# protoCuantumv2_1.net
KiCad netlist of a schematic drawn in EAGLE
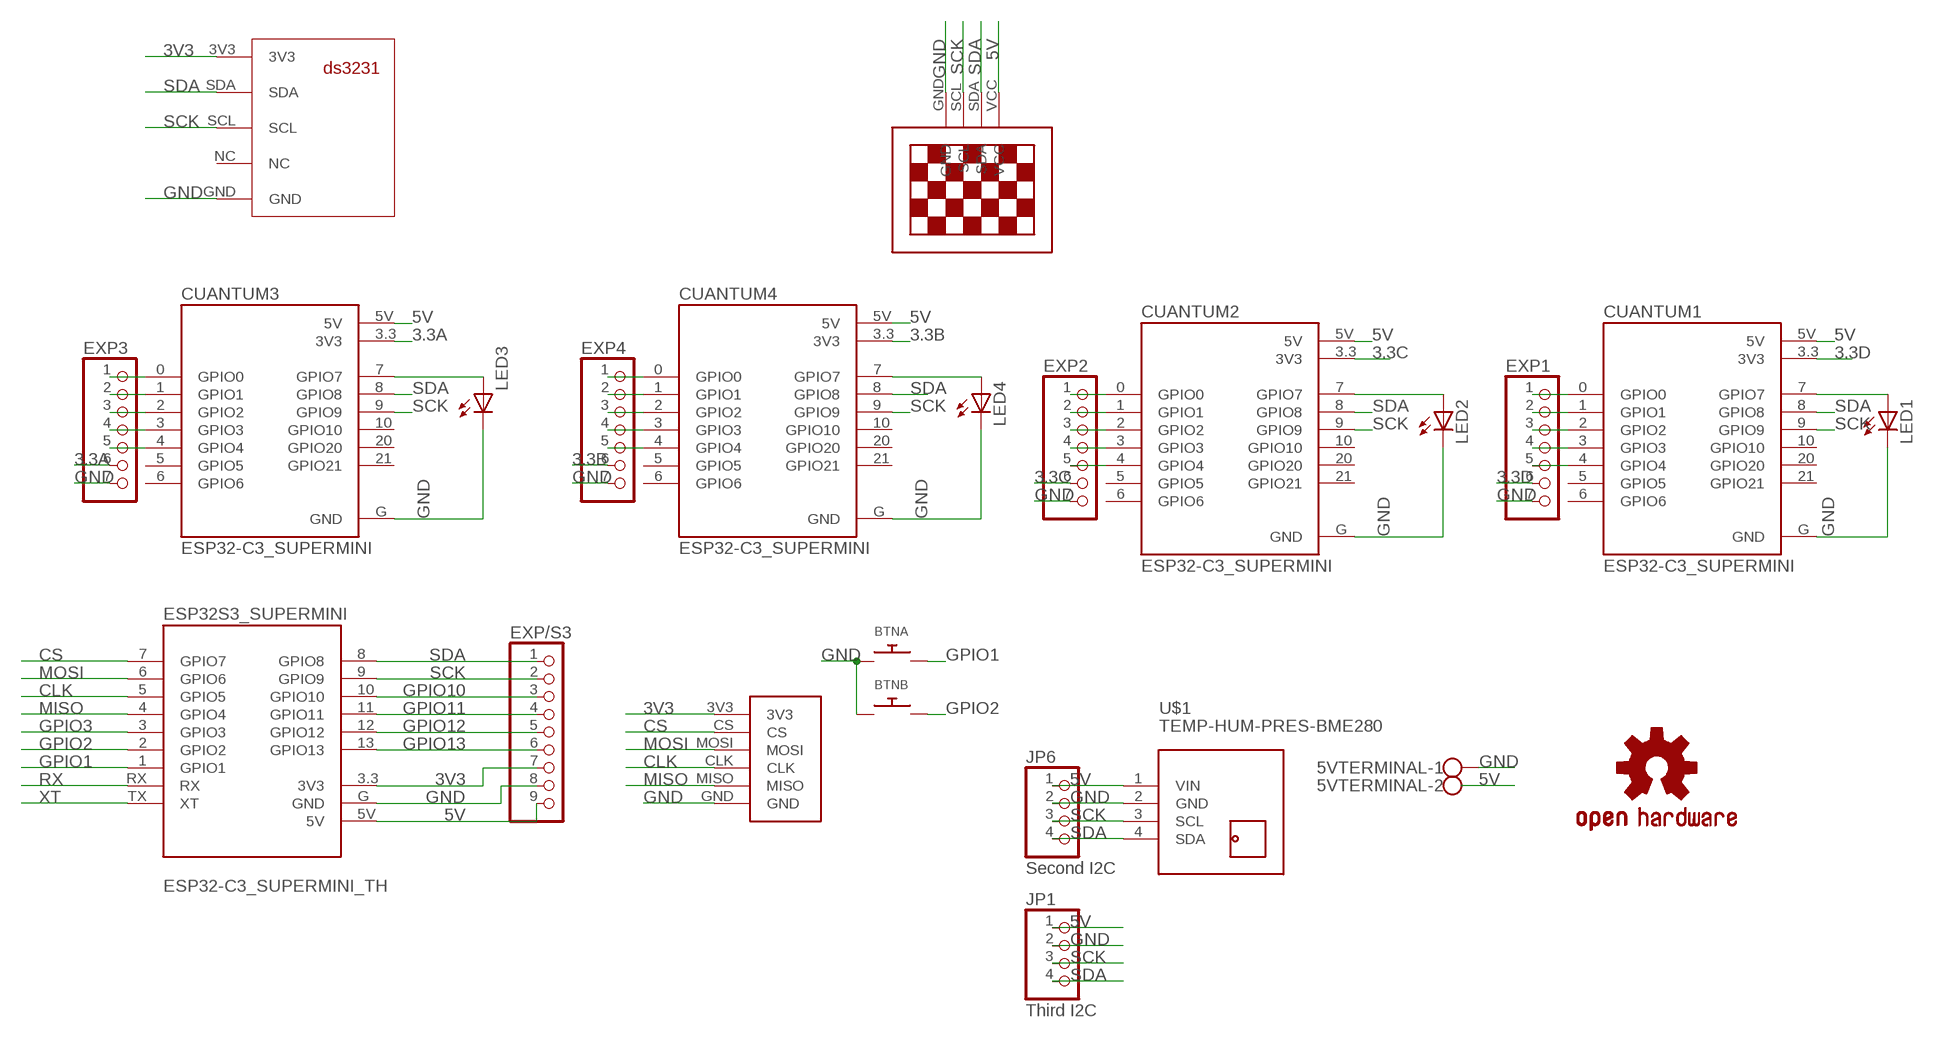
[diagram p0: schematic, sheet 1]

(export (version "E")
  (design (tool "Eeschema 10.0.6"))
  (components
    (comp (ref "5VTERMINAL")
      (value "W237-102")
      (footprint "eagle-import:W237-102")
      (fields (field (name "MPN") "237-102"))
      (libsource (lib "eagle-import") (part "W237-102"))
    )
    (comp (ref "BTNA")
      (value "SWITCH_PUSHBUTTONEVQ-PE")
      (footprint "eagle-import:TACT_PANA-EVQ")
      (libsource (lib "eagle-import") (part "SWITCH_PUSHBUTTONEVQ-PE"))
    )
    (comp (ref "BTNB")
      (value "SWITCH_PUSHBUTTONEVQ-PE")
      (footprint "eagle-import:TACT_PANA-EVQ")
      (libsource (lib "eagle-import") (part "SWITCH_PUSHBUTTONEVQ-PE"))
    )
    (comp (ref "CUANTUM1")
      (value "ESP32-C3_SUPERMINI")
      (footprint "eagle-import:MODULE_ESP32-C3_SUPERMINI_TH")
      (fields (field (name "MF") "Espressif Systems") (field (name "MP") "ESP32-C3 SuperMini_TH"))
      (libsource (lib "eagle-import") (part "ESP32-C3_SUPERMINI_TH"))
    )
    (comp (ref "CUANTUM2")
      (value "ESP32-C3_SUPERMINI")
      (footprint "eagle-import:MODULE_ESP32-C3_SUPERMINI_TH")
      (fields (field (name "MF") "Espressif Systems") (field (name "MP") "ESP32-C3 SuperMini_TH"))
      (libsource (lib "eagle-import") (part "ESP32-C3_SUPERMINI_TH"))
    )
    (comp (ref "CUANTUM3")
      (value "ESP32-C3_SUPERMINI")
      (footprint "eagle-import:MODULE_ESP32-C3_SUPERMINI_TH")
      (fields (field (name "MF") "Espressif Systems") (field (name "MP") "ESP32-C3 SuperMini_TH"))
      (libsource (lib "eagle-import") (part "ESP32-C3_SUPERMINI_TH"))
    )
    (comp (ref "CUANTUM4")
      (value "ESP32-C3_SUPERMINI")
      (footprint "eagle-import:MODULE_ESP32-C3_SUPERMINI_TH")
      (fields (field (name "MF") "Espressif Systems") (field (name "MP") "ESP32-C3 SuperMini_TH"))
      (libsource (lib "eagle-import") (part "ESP32-C3_SUPERMINI_TH"))
    )
    (comp (ref "ESP32S3_SUPERMINI")
      (value "ESP32-C3_SUPERMINI_TH")
      (footprint "eagle-import:MODULE_ESP32-C3_SUPERMINI_TH")
      (fields (field (name "MF") "Espressif Systems") (field (name "MP") "ESP32-S3 SuperMini_TH"))
      (libsource (lib "eagle-import") (part "ESP32-S3_SUPERMINI_TH_ESP32-C3_SUPERMINI_TH"))
    )
    (comp (ref "EXP/S3")
      (value "PINHD-1X9")
      (footprint "eagle-import:1X09")
      (libsource (lib "eagle-import") (part "PINHD-1X9"))
    )
    (comp (ref "EXP1")
      (value "PINHD-1X7")
      (footprint "eagle-import:1X07")
      (libsource (lib "eagle-import") (part "PINHD-1X7"))
    )
    (comp (ref "EXP2")
      (value "PINHD-1X7")
      (footprint "eagle-import:1X07")
      (libsource (lib "eagle-import") (part "PINHD-1X7"))
    )
    (comp (ref "EXP3")
      (value "PINHD-1X7")
      (footprint "eagle-import:1X07")
      (libsource (lib "eagle-import") (part "PINHD-1X7"))
    )
    (comp (ref "EXP4")
      (value "PINHD-1X7")
      (footprint "eagle-import:1X07")
      (libsource (lib "eagle-import") (part "PINHD-1X7"))
    )
    (comp (ref "JP1")
      (value "Third I2C")
      (footprint "eagle-import:1X04")
      (libsource (lib "eagle-import") (part "PINHD-1X4"))
    )
    (comp (ref "JP6")
      (value "Second I2C")
      (footprint "eagle-import:1X04")
      (libsource (lib "eagle-import") (part "PINHD-1X4"))
    )
    (comp (ref "LED1")
      (value "LED3MM")
      (footprint "eagle-import:LED3MM")
      (libsource (lib "eagle-import") (part "LED3MM"))
    )
    (comp (ref "LED2")
      (value "LED3MM")
      (footprint "eagle-import:LED3MM")
      (libsource (lib "eagle-import") (part "LED3MM"))
    )
    (comp (ref "LED3")
      (value "LED3MM")
      (footprint "eagle-import:LED3MM")
      (libsource (lib "eagle-import") (part "LED3MM"))
    )
    (comp (ref "LED4")
      (value "LED3MM")
      (footprint "eagle-import:LED3MM")
      (libsource (lib "eagle-import") (part "LED3MM"))
    )
    (comp (ref "LOGO1")
      (value "OSHW-LOGOM")
      (footprint "eagle-import:OSHW-LOGO-M")
      (libsource (lib "eagle-import") (part "OSHW-LOGOM"))
    )
    (comp (ref "OLED1.3")
      (value "13\"OLED13\"OLED")
      (footprint "eagle-import:1.3_OLED")
      (libsource (lib "eagle-import") (part "13{dblquote}OLED13{dblquote}OLED"))
    )
    (comp (ref "U$1")
      (value "TEMP-HUM-PRES-BME280")
      (footprint "eagle-import:TEMP-HUM-PRES-BME280")
      (libsource (lib "eagle-import") (part "TEMP-HUM-PRES-BME280"))
    )
    (comp (ref "U$2")
      (value "SD_KUSKALLA")
      (footprint "eagle-import:SD_KUSKALLA")
      (libsource (lib "eagle-import") (part "SD_KUSKALLA"))
    )
    (comp (ref "U$4")
      (value "RTC")
      (footprint "eagle-import:RTCDS3231FP")
      (libsource (lib "eagle-import") (part "RTC"))
    )
  )
  (nets
    (net (code "1") (name "/3.3A") (class "Default")
      (node (ref "CUANTUM3") (pin "3.3") (pinfunction "3V3_3.3") (pintype "power_in"))
      (node (ref "EXP3") (pin "6") (pinfunction "6_6") (pintype "passive"))
    )
    (net (code "2") (name "/3.3B") (class "Default")
      (node (ref "CUANTUM4") (pin "3.3") (pinfunction "3V3_3.3") (pintype "power_in"))
      (node (ref "EXP4") (pin "6") (pinfunction "6_6") (pintype "passive"))
    )
    (net (code "3") (name "/3.3C") (class "Default")
      (node (ref "CUANTUM2") (pin "3.3") (pinfunction "3V3_3.3") (pintype "power_in"))
      (node (ref "EXP2") (pin "6") (pinfunction "6_6") (pintype "passive"))
    )
    (net (code "4") (name "/3.3D") (class "Default")
      (node (ref "CUANTUM1") (pin "3.3") (pinfunction "3V3_3.3") (pintype "power_in"))
      (node (ref "EXP1") (pin "6") (pinfunction "6_6") (pintype "passive"))
    )
    (net (code "5") (name "/3V3") (class "Default")
      (node (ref "ESP32S3_SUPERMINI") (pin "3.3") (pinfunction "3V3_3.3") (pintype "power_in"))
      (node (ref "EXP/S3") (pin "7") (pinfunction "7_7") (pintype "passive"))
      (node (ref "U$2") (pin "3V3") (pinfunction "3V3_3V3") (pintype "bidirectional"))
      (node (ref "U$4") (pin "3V3") (pinfunction "3V3_3V3") (pintype "bidirectional"))
    )
    (net (code "6") (name "/5V") (class "Default")
      (node (ref "5VTERMINAL") (pin "2") (pinfunction "KL_2") (pintype "passive"))
      (node (ref "CUANTUM1") (pin "5V") (pinfunction "5V_5V") (pintype "power_in"))
      (node (ref "CUANTUM2") (pin "5V") (pinfunction "5V_5V") (pintype "power_in"))
      (node (ref "CUANTUM3") (pin "5V") (pinfunction "5V_5V") (pintype "power_in"))
      (node (ref "CUANTUM4") (pin "5V") (pinfunction "5V_5V") (pintype "power_in"))
      (node (ref "ESP32S3_SUPERMINI") (pin "5V") (pinfunction "5V_5V") (pintype "power_in"))
      (node (ref "EXP/S3") (pin "9") (pinfunction "9_9") (pintype "passive"))
      (node (ref "JP1") (pin "1") (pinfunction "1_1") (pintype "passive"))
      (node (ref "JP6") (pin "1") (pinfunction "1_1") (pintype "passive"))
      (node (ref "OLED1.3") (pin "VCC") (pinfunction "VCC_VCC") (pintype "bidirectional"))
      (node (ref "U$1") (pin "1") (pinfunction "VIN_1") (pintype "power_in"))
    )
    (net (code "7") (name "/CLK") (class "Default")
      (node (ref "ESP32S3_SUPERMINI") (pin "5") (pinfunction "GPIO5_5") (pintype "bidirectional"))
      (node (ref "U$2") (pin "CLK") (pinfunction "CLK_CLK") (pintype "bidirectional"))
    )
    (net (code "8") (name "/CS") (class "Default")
      (node (ref "ESP32S3_SUPERMINI") (pin "7") (pinfunction "GPIO7_7") (pintype "bidirectional"))
      (node (ref "U$2") (pin "CS") (pinfunction "CS_CS") (pintype "bidirectional"))
    )
    (net (code "9") (name "/GND") (class "Default")
      (node (ref "5VTERMINAL") (pin "1") (pinfunction "KL_1") (pintype "passive"))
      (node (ref "BTNA") (pin "P$1") (pinfunction "P$1_P$1") (pintype "passive"))
      (node (ref "BTNB") (pin "P$1") (pinfunction "P$1_P$1") (pintype "passive"))
      (node (ref "CUANTUM1") (pin "G") (pinfunction "GND_G") (pintype "power_in"))
      (node (ref "CUANTUM2") (pin "G") (pinfunction "GND_G") (pintype "power_in"))
      (node (ref "CUANTUM3") (pin "G") (pinfunction "GND_G") (pintype "power_in"))
      (node (ref "CUANTUM4") (pin "G") (pinfunction "GND_G") (pintype "power_in"))
      (node (ref "ESP32S3_SUPERMINI") (pin "G") (pinfunction "GND_G") (pintype "power_in"))
      (node (ref "EXP/S3") (pin "8") (pinfunction "8_8") (pintype "passive"))
      (node (ref "EXP1") (pin "7") (pinfunction "7_7") (pintype "passive"))
      (node (ref "EXP2") (pin "7") (pinfunction "7_7") (pintype "passive"))
      (node (ref "EXP3") (pin "7") (pinfunction "7_7") (pintype "passive"))
      (node (ref "EXP4") (pin "7") (pinfunction "7_7") (pintype "passive"))
      (node (ref "JP1") (pin "2") (pinfunction "2_2") (pintype "passive"))
      (node (ref "JP6") (pin "2") (pinfunction "2_2") (pintype "passive"))
      (node (ref "LED1") (pin "K") (pinfunction "C_K") (pintype "passive"))
      (node (ref "LED2") (pin "K") (pinfunction "C_K") (pintype "passive"))
      (node (ref "LED3") (pin "K") (pinfunction "C_K") (pintype "passive"))
      (node (ref "LED4") (pin "K") (pinfunction "C_K") (pintype "passive"))
      (node (ref "OLED1.3") (pin "GND") (pinfunction "GND_GND") (pintype "bidirectional"))
      (node (ref "U$1") (pin "2") (pinfunction "GND_2") (pintype "power_in"))
      (node (ref "U$2") (pin "GND") (pinfunction "GND_GND") (pintype "bidirectional"))
      (node (ref "U$4") (pin "GND") (pinfunction "GND_GND") (pintype "bidirectional"))
    )
    (net (code "10") (name "/GPIO1") (class "Default")
      (node (ref "BTNA") (pin "P$2") (pinfunction "P$2_P$2") (pintype "passive"))
      (node (ref "ESP32S3_SUPERMINI") (pin "1") (pinfunction "GPIO1_1") (pintype "bidirectional"))
    )
    (net (code "11") (name "/GPIO2") (class "Default")
      (node (ref "BTNB") (pin "P$2") (pinfunction "P$2_P$2") (pintype "passive"))
      (node (ref "ESP32S3_SUPERMINI") (pin "2") (pinfunction "GPIO2_2") (pintype "bidirectional"))
    )
    (net (code "12") (name "/GPIO3") (class "Default")
      (node (ref "ESP32S3_SUPERMINI") (pin "3") (pinfunction "GPIO3_3") (pintype "bidirectional"))
    )
    (net (code "13") (name "/GPIO10") (class "Default")
      (node (ref "ESP32S3_SUPERMINI") (pin "10") (pinfunction "GPIO10_10") (pintype "bidirectional"))
      (node (ref "EXP/S3") (pin "3") (pinfunction "3_3") (pintype "passive"))
    )
    (net (code "14") (name "/GPIO11") (class "Default")
      (node (ref "ESP32S3_SUPERMINI") (pin "11") (pinfunction "GPIO11_11") (pintype "bidirectional"))
      (node (ref "EXP/S3") (pin "4") (pinfunction "4_4") (pintype "passive"))
    )
    (net (code "15") (name "/GPIO12") (class "Default")
      (node (ref "ESP32S3_SUPERMINI") (pin "12") (pinfunction "GPIO12_12") (pintype "bidirectional"))
      (node (ref "EXP/S3") (pin "5") (pinfunction "5_5") (pintype "passive"))
    )
    (net (code "16") (name "/GPIO13") (class "Default")
      (node (ref "ESP32S3_SUPERMINI") (pin "13") (pinfunction "GPIO13_13") (pintype "bidirectional"))
      (node (ref "EXP/S3") (pin "6") (pinfunction "6_6") (pintype "passive"))
    )
    (net (code "17") (name "/MISO") (class "Default")
      (node (ref "ESP32S3_SUPERMINI") (pin "4") (pinfunction "GPIO4_4") (pintype "bidirectional"))
      (node (ref "U$2") (pin "MISO") (pinfunction "MISO_MISO") (pintype "bidirectional"))
    )
    (net (code "18") (name "/MOSI") (class "Default")
      (node (ref "ESP32S3_SUPERMINI") (pin "6") (pinfunction "GPIO6_6") (pintype "bidirectional"))
      (node (ref "U$2") (pin "MOSI") (pinfunction "MOSI_MOSI") (pintype "bidirectional"))
    )
    (net (code "19") (name "/RX") (class "Default")
      (node (ref "ESP32S3_SUPERMINI") (pin "RX") (pinfunction "RX_RX") (pintype "bidirectional"))
    )
    (net (code "20") (name "/SCK") (class "Default")
      (node (ref "CUANTUM1") (pin "9") (pinfunction "GPIO9_9") (pintype "bidirectional"))
      (node (ref "CUANTUM2") (pin "9") (pinfunction "GPIO9_9") (pintype "bidirectional"))
      (node (ref "CUANTUM3") (pin "9") (pinfunction "GPIO9_9") (pintype "bidirectional"))
      (node (ref "CUANTUM4") (pin "9") (pinfunction "GPIO9_9") (pintype "bidirectional"))
      (node (ref "ESP32S3_SUPERMINI") (pin "9") (pinfunction "GPIO9_9") (pintype "bidirectional"))
      (node (ref "EXP/S3") (pin "2") (pinfunction "2_2") (pintype "passive"))
      (node (ref "JP1") (pin "3") (pinfunction "3_3") (pintype "passive"))
      (node (ref "JP6") (pin "3") (pinfunction "3_3") (pintype "passive"))
      (node (ref "OLED1.3") (pin "SCL") (pinfunction "SCL_SCL") (pintype "bidirectional"))
      (node (ref "U$1") (pin "3") (pinfunction "SCL_3") (pintype "bidirectional"))
      (node (ref "U$4") (pin "SCL") (pinfunction "SCL_SCL") (pintype "bidirectional"))
    )
    (net (code "21") (name "/SDA") (class "Default")
      (node (ref "CUANTUM1") (pin "8") (pinfunction "GPIO8_8") (pintype "bidirectional"))
      (node (ref "CUANTUM2") (pin "8") (pinfunction "GPIO8_8") (pintype "bidirectional"))
      (node (ref "CUANTUM3") (pin "8") (pinfunction "GPIO8_8") (pintype "bidirectional"))
      (node (ref "CUANTUM4") (pin "8") (pinfunction "GPIO8_8") (pintype "bidirectional"))
      (node (ref "ESP32S3_SUPERMINI") (pin "8") (pinfunction "GPIO8_8") (pintype "bidirectional"))
      (node (ref "EXP/S3") (pin "1") (pinfunction "1_1") (pintype "passive"))
      (node (ref "JP1") (pin "4") (pinfunction "4_4") (pintype "passive"))
      (node (ref "JP6") (pin "4") (pinfunction "4_4") (pintype "passive"))
      (node (ref "OLED1.3") (pin "SDA") (pinfunction "SDA_SDA") (pintype "bidirectional"))
      (node (ref "U$1") (pin "4") (pinfunction "SDA_4") (pintype "bidirectional"))
      (node (ref "U$4") (pin "SDA") (pinfunction "SDA_SDA") (pintype "bidirectional"))
    )
    (net (code "22") (name "/XT") (class "Default")
      (node (ref "ESP32S3_SUPERMINI") (pin "TX") (pinfunction "XT_TX") (pintype "bidirectional"))
    )
    (net (code "23") (name "Net-(CUANTUM1-GPIO0)") (class "Default")
      (node (ref "CUANTUM1") (pin "0") (pinfunction "GPIO0_0") (pintype "bidirectional"))
      (node (ref "EXP1") (pin "1") (pinfunction "1_1") (pintype "passive"))
    )
    (net (code "24") (name "Net-(CUANTUM1-GPIO1)") (class "Default")
      (node (ref "CUANTUM1") (pin "1") (pinfunction "GPIO1_1") (pintype "bidirectional"))
      (node (ref "EXP1") (pin "2") (pinfunction "2_2") (pintype "passive"))
    )
    (net (code "25") (name "Net-(CUANTUM1-GPIO2)") (class "Default")
      (node (ref "CUANTUM1") (pin "2") (pinfunction "GPIO2_2") (pintype "bidirectional"))
      (node (ref "EXP1") (pin "3") (pinfunction "3_3") (pintype "passive"))
    )
    (net (code "26") (name "Net-(CUANTUM1-GPIO3)") (class "Default")
      (node (ref "CUANTUM1") (pin "3") (pinfunction "GPIO3_3") (pintype "bidirectional"))
      (node (ref "EXP1") (pin "4") (pinfunction "4_4") (pintype "passive"))
    )
    (net (code "27") (name "Net-(CUANTUM1-GPIO4)") (class "Default")
      (node (ref "CUANTUM1") (pin "4") (pinfunction "GPIO4_4") (pintype "bidirectional"))
      (node (ref "EXP1") (pin "5") (pinfunction "5_5") (pintype "passive"))
    )
    (net (code "28") (name "Net-(CUANTUM1-GPIO7)") (class "Default")
      (node (ref "CUANTUM1") (pin "7") (pinfunction "GPIO7_7") (pintype "bidirectional"))
      (node (ref "LED1") (pin "A") (pinfunction "A_A") (pintype "passive"))
    )
    (net (code "29") (name "Net-(CUANTUM2-GPIO0)") (class "Default")
      (node (ref "CUANTUM2") (pin "0") (pinfunction "GPIO0_0") (pintype "bidirectional"))
      (node (ref "EXP2") (pin "1") (pinfunction "1_1") (pintype "passive"))
    )
    (net (code "30") (name "Net-(CUANTUM2-GPIO1)") (class "Default")
      (node (ref "CUANTUM2") (pin "1") (pinfunction "GPIO1_1") (pintype "bidirectional"))
      (node (ref "EXP2") (pin "2") (pinfunction "2_2") (pintype "passive"))
    )
    (net (code "31") (name "Net-(CUANTUM2-GPIO2)") (class "Default")
      (node (ref "CUANTUM2") (pin "2") (pinfunction "GPIO2_2") (pintype "bidirectional"))
      (node (ref "EXP2") (pin "3") (pinfunction "3_3") (pintype "passive"))
    )
    (net (code "32") (name "Net-(CUANTUM2-GPIO3)") (class "Default")
      (node (ref "CUANTUM2") (pin "3") (pinfunction "GPIO3_3") (pintype "bidirectional"))
      (node (ref "EXP2") (pin "4") (pinfunction "4_4") (pintype "passive"))
    )
    (net (code "33") (name "Net-(CUANTUM2-GPIO4)") (class "Default")
      (node (ref "CUANTUM2") (pin "4") (pinfunction "GPIO4_4") (pintype "bidirectional"))
      (node (ref "EXP2") (pin "5") (pinfunction "5_5") (pintype "passive"))
    )
    (net (code "34") (name "Net-(CUANTUM2-GPIO7)") (class "Default")
      (node (ref "CUANTUM2") (pin "7") (pinfunction "GPIO7_7") (pintype "bidirectional"))
      (node (ref "LED2") (pin "A") (pinfunction "A_A") (pintype "passive"))
    )
    (net (code "35") (name "Net-(CUANTUM3-GPIO0)") (class "Default")
      (node (ref "CUANTUM3") (pin "0") (pinfunction "GPIO0_0") (pintype "bidirectional"))
      (node (ref "EXP3") (pin "1") (pinfunction "1_1") (pintype "passive"))
    )
    (net (code "36") (name "Net-(CUANTUM3-GPIO1)") (class "Default")
      (node (ref "CUANTUM3") (pin "1") (pinfunction "GPIO1_1") (pintype "bidirectional"))
      (node (ref "EXP3") (pin "2") (pinfunction "2_2") (pintype "passive"))
    )
    (net (code "37") (name "Net-(CUANTUM3-GPIO2)") (class "Default")
      (node (ref "CUANTUM3") (pin "2") (pinfunction "GPIO2_2") (pintype "bidirectional"))
      (node (ref "EXP3") (pin "3") (pinfunction "3_3") (pintype "passive"))
    )
    (net (code "38") (name "Net-(CUANTUM3-GPIO3)") (class "Default")
      (node (ref "CUANTUM3") (pin "3") (pinfunction "GPIO3_3") (pintype "bidirectional"))
      (node (ref "EXP3") (pin "4") (pinfunction "4_4") (pintype "passive"))
    )
    (net (code "39") (name "Net-(CUANTUM3-GPIO4)") (class "Default")
      (node (ref "CUANTUM3") (pin "4") (pinfunction "GPIO4_4") (pintype "bidirectional"))
      (node (ref "EXP3") (pin "5") (pinfunction "5_5") (pintype "passive"))
    )
    (net (code "40") (name "Net-(CUANTUM3-GPIO7)") (class "Default")
      (node (ref "CUANTUM3") (pin "7") (pinfunction "GPIO7_7") (pintype "bidirectional"))
      (node (ref "LED3") (pin "A") (pinfunction "A_A") (pintype "passive"))
    )
    (net (code "41") (name "Net-(CUANTUM4-GPIO0)") (class "Default")
      (node (ref "CUANTUM4") (pin "0") (pinfunction "GPIO0_0") (pintype "bidirectional"))
      (node (ref "EXP4") (pin "1") (pinfunction "1_1") (pintype "passive"))
    )
    (net (code "42") (name "Net-(CUANTUM4-GPIO1)") (class "Default")
      (node (ref "CUANTUM4") (pin "1") (pinfunction "GPIO1_1") (pintype "bidirectional"))
      (node (ref "EXP4") (pin "2") (pinfunction "2_2") (pintype "passive"))
    )
    (net (code "43") (name "Net-(CUANTUM4-GPIO2)") (class "Default")
      (node (ref "CUANTUM4") (pin "2") (pinfunction "GPIO2_2") (pintype "bidirectional"))
      (node (ref "EXP4") (pin "3") (pinfunction "3_3") (pintype "passive"))
    )
    (net (code "44") (name "Net-(CUANTUM4-GPIO3)") (class "Default")
      (node (ref "CUANTUM4") (pin "3") (pinfunction "GPIO3_3") (pintype "bidirectional"))
      (node (ref "EXP4") (pin "4") (pinfunction "4_4") (pintype "passive"))
    )
    (net (code "45") (name "Net-(CUANTUM4-GPIO4)") (class "Default")
      (node (ref "CUANTUM4") (pin "4") (pinfunction "GPIO4_4") (pintype "bidirectional"))
      (node (ref "EXP4") (pin "5") (pinfunction "5_5") (pintype "passive"))
    )
    (net (code "46") (name "Net-(CUANTUM4-GPIO7)") (class "Default")
      (node (ref "CUANTUM4") (pin "7") (pinfunction "GPIO7_7") (pintype "bidirectional"))
      (node (ref "LED4") (pin "A") (pinfunction "A_A") (pintype "passive"))
    )
    (net (code "47") (name "unconnected-(CUANTUM1-GPIO5-Pad5)") (class "Default")
      (node (ref "CUANTUM1") (pin "5") (pinfunction "GPIO5_5") (pintype "bidirectional"))
    )
    (net (code "48") (name "unconnected-(CUANTUM1-GPIO6-Pad6)") (class "Default")
      (node (ref "CUANTUM1") (pin "6") (pinfunction "GPIO6_6") (pintype "bidirectional"))
    )
    (net (code "49") (name "unconnected-(CUANTUM1-GPIO10-Pad10)") (class "Default")
      (node (ref "CUANTUM1") (pin "10") (pinfunction "GPIO10_10") (pintype "bidirectional"))
    )
    (net (code "50") (name "unconnected-(CUANTUM1-GPIO20-Pad20)") (class "Default")
      (node (ref "CUANTUM1") (pin "20") (pinfunction "GPIO20_20") (pintype "bidirectional"))
    )
    (net (code "51") (name "unconnected-(CUANTUM1-GPIO21-Pad21)") (class "Default")
      (node (ref "CUANTUM1") (pin "21") (pinfunction "GPIO21_21") (pintype "bidirectional"))
    )
    (net (code "52") (name "unconnected-(CUANTUM2-GPIO5-Pad5)") (class "Default")
      (node (ref "CUANTUM2") (pin "5") (pinfunction "GPIO5_5") (pintype "bidirectional"))
    )
    (net (code "53") (name "unconnected-(CUANTUM2-GPIO6-Pad6)") (class "Default")
      (node (ref "CUANTUM2") (pin "6") (pinfunction "GPIO6_6") (pintype "bidirectional"))
    )
    (net (code "54") (name "unconnected-(CUANTUM2-GPIO10-Pad10)") (class "Default")
      (node (ref "CUANTUM2") (pin "10") (pinfunction "GPIO10_10") (pintype "bidirectional"))
    )
    (net (code "55") (name "unconnected-(CUANTUM2-GPIO20-Pad20)") (class "Default")
      (node (ref "CUANTUM2") (pin "20") (pinfunction "GPIO20_20") (pintype "bidirectional"))
    )
    (net (code "56") (name "unconnected-(CUANTUM2-GPIO21-Pad21)") (class "Default")
      (node (ref "CUANTUM2") (pin "21") (pinfunction "GPIO21_21") (pintype "bidirectional"))
    )
    (net (code "57") (name "unconnected-(CUANTUM3-GPIO5-Pad5)") (class "Default")
      (node (ref "CUANTUM3") (pin "5") (pinfunction "GPIO5_5") (pintype "bidirectional"))
    )
    (net (code "58") (name "unconnected-(CUANTUM3-GPIO6-Pad6)") (class "Default")
      (node (ref "CUANTUM3") (pin "6") (pinfunction "GPIO6_6") (pintype "bidirectional"))
    )
    (net (code "59") (name "unconnected-(CUANTUM3-GPIO10-Pad10)") (class "Default")
      (node (ref "CUANTUM3") (pin "10") (pinfunction "GPIO10_10") (pintype "bidirectional"))
    )
    (net (code "60") (name "unconnected-(CUANTUM3-GPIO20-Pad20)") (class "Default")
      (node (ref "CUANTUM3") (pin "20") (pinfunction "GPIO20_20") (pintype "bidirectional"))
    )
    (net (code "61") (name "unconnected-(CUANTUM3-GPIO21-Pad21)") (class "Default")
      (node (ref "CUANTUM3") (pin "21") (pinfunction "GPIO21_21") (pintype "bidirectional"))
    )
    (net (code "62") (name "unconnected-(CUANTUM4-GPIO5-Pad5)") (class "Default")
      (node (ref "CUANTUM4") (pin "5") (pinfunction "GPIO5_5") (pintype "bidirectional"))
    )
    (net (code "63") (name "unconnected-(CUANTUM4-GPIO6-Pad6)") (class "Default")
      (node (ref "CUANTUM4") (pin "6") (pinfunction "GPIO6_6") (pintype "bidirectional"))
    )
    (net (code "64") (name "unconnected-(CUANTUM4-GPIO10-Pad10)") (class "Default")
      (node (ref "CUANTUM4") (pin "10") (pinfunction "GPIO10_10") (pintype "bidirectional"))
    )
    (net (code "65") (name "unconnected-(CUANTUM4-GPIO20-Pad20)") (class "Default")
      (node (ref "CUANTUM4") (pin "20") (pinfunction "GPIO20_20") (pintype "bidirectional"))
    )
    (net (code "66") (name "unconnected-(CUANTUM4-GPIO21-Pad21)") (class "Default")
      (node (ref "CUANTUM4") (pin "21") (pinfunction "GPIO21_21") (pintype "bidirectional"))
    )
    (net (code "67") (name "unconnected-(U$4-PadNC)") (class "Default")
      (node (ref "U$4") (pin "NC") (pinfunction "NC_NC") (pintype "bidirectional"))
    )
  )
)
